# LED_Adapter.net
KiCad netlist of a schematic drawn in Altium Designer
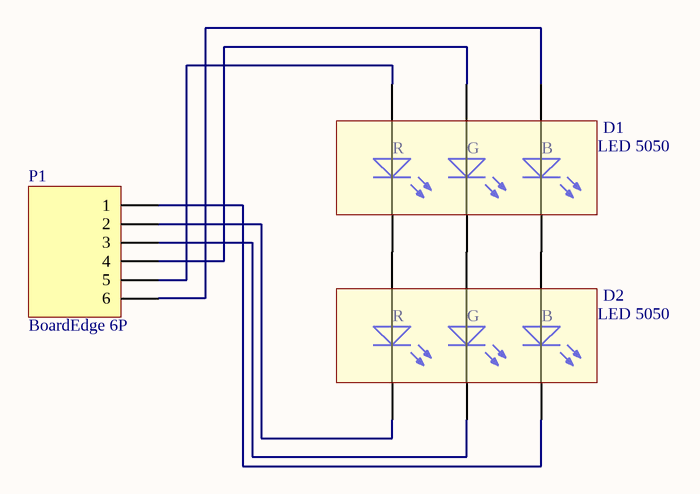
[diagram p0: LED_Adapter.SchDoc]

(export (version "E")
  (design (tool "Eeschema 10.0.6"))
  (components
    (comp (ref "D1")
      (value "LED 5050")
      (footprint "PLCC6")
      (description "SMD PLCC-6 20mA 5050")
      (libsource (lib "HQ_Library") (part "LED RGB 5050"))
    )
    (comp (ref "D2")
      (value "LED 5050")
      (footprint "PLCC6")
      (description "SMD PLCC-6 20mA 5050")
      (libsource (lib "HQ_Library") (part "LED RGB 5050"))
    )
    (comp (ref "P1")
      (value "BoardEdge 6P")
      (footprint "BoardEdge Layout 12P Single Side M")
      (description "Layout BoardEdge 6P Single Side TE 7-5530843-6")
      (libsource (lib "HQ_Library") (part "BoardEdge Layout  SS 6P"))
    )
  )
  (nets
    (net (code "1") (name "Net-(D1-A_B)") (class "Default")
      (node (ref "D1") (pin "6") (pinfunction "A_B_6") (pintype "passive"))
      (node (ref "P1") (pin "6") (pinfunction "6_6") (pintype "passive"))
    )
    (net (code "2") (name "Net-(D1-A_G)") (class "Default")
      (node (ref "D1") (pin "4") (pinfunction "A_G_4") (pintype "passive"))
      (node (ref "P1") (pin "4") (pinfunction "4_4") (pintype "passive"))
    )
    (net (code "3") (name "Net-(D1-A_R)") (class "Default")
      (node (ref "D1") (pin "2") (pinfunction "A_R_2") (pintype "passive"))
      (node (ref "P1") (pin "5") (pinfunction "5_5") (pintype "passive"))
    )
    (net (code "4") (name "Net-(D1-K_B)") (class "Default")
      (node (ref "D1") (pin "5") (pinfunction "K_B_5") (pintype "passive"))
      (node (ref "D2") (pin "6") (pinfunction "A_B_6") (pintype "passive"))
    )
    (net (code "5") (name "Net-(D1-K_G)") (class "Default")
      (node (ref "D1") (pin "3") (pinfunction "K_G_3") (pintype "passive"))
      (node (ref "D2") (pin "4") (pinfunction "A_G_4") (pintype "passive"))
    )
    (net (code "6") (name "Net-(D1-K_R)") (class "Default")
      (node (ref "D1") (pin "1") (pinfunction "K_R_1") (pintype "passive"))
      (node (ref "D2") (pin "2") (pinfunction "A_R_2") (pintype "passive"))
    )
    (net (code "7") (name "Net-(D2-K_B)") (class "Default")
      (node (ref "D2") (pin "5") (pinfunction "K_B_5") (pintype "passive"))
      (node (ref "P1") (pin "1") (pinfunction "1_1") (pintype "passive"))
    )
    (net (code "8") (name "Net-(D2-K_G)") (class "Default")
      (node (ref "D2") (pin "3") (pinfunction "K_G_3") (pintype "passive"))
      (node (ref "P1") (pin "3") (pinfunction "3_3") (pintype "passive"))
    )
    (net (code "9") (name "Net-(D2-K_R)") (class "Default")
      (node (ref "D2") (pin "1") (pinfunction "K_R_1") (pintype "passive"))
      (node (ref "P1") (pin "2") (pinfunction "2_2") (pintype "passive"))
    )
  )
)
